# 14_-_BOT_BOARD_HEADER.net
KiCad netlist of a schematic drawn in Altium Designer
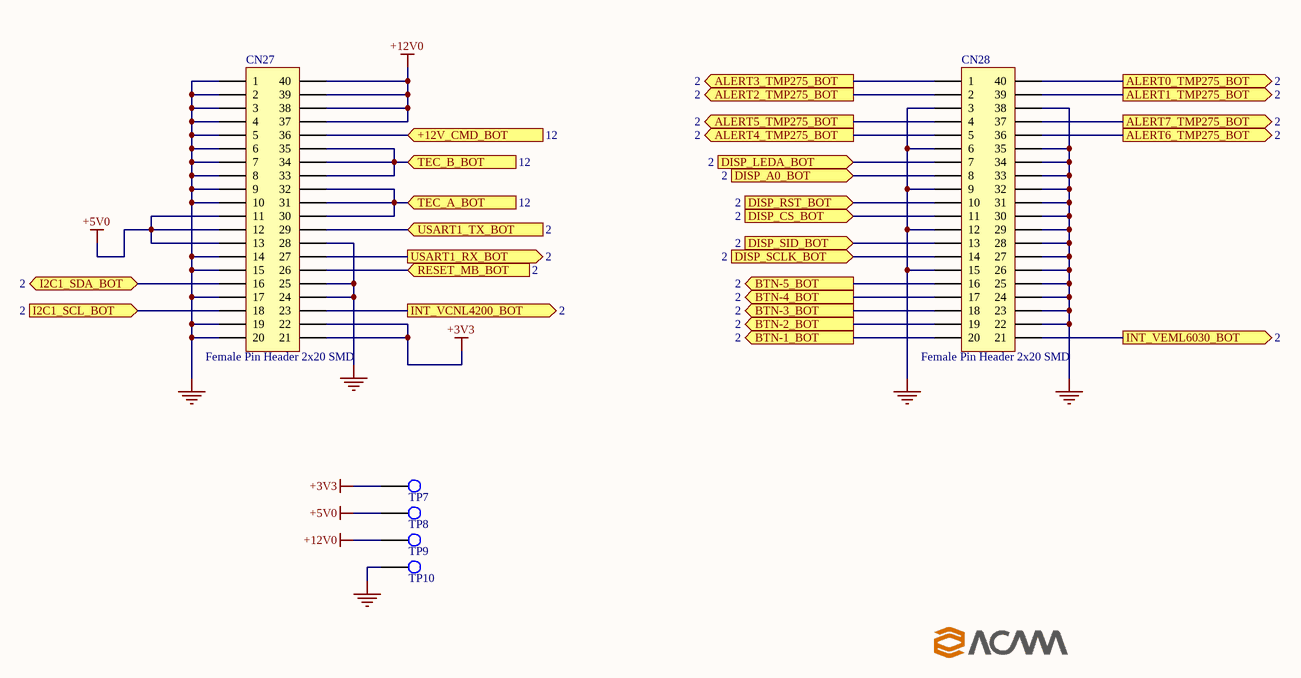
[diagram p0: [14] - BOT BOARD HEADER.SchDoc]

(export (version "E")
  (design (tool "Eeschema 10.0.6"))
  (components
    (comp (ref "CN27")
      (value "Female Pin Header 2x20 SMD")
      (footprint "HEADER_FEMALE_SMD_2x20")
      (description "SMD Female Pin Header 2.54mm Pitch, 2x20")
      (libsource (lib "Farzan Custom Library") (part "Pin header Female 2x20 smd"))
    )
    (comp (ref "CN28")
      (value "Female Pin Header 2x20 SMD")
      (footprint "HEADER_FEMALE_SMD_2x20")
      (description "SMD Female Pin Header 2.54mm Pitch, 2x20")
      (libsource (lib "Farzan Custom Library") (part "Pin header Female 2x20 smd"))
    )
    (comp (ref "TP7")
      (value "Test Point")
      (footprint "PIN_2mm")
      (description "Test Point Footprint")
      (libsource (lib "Farzan Custom Library") (part "Test Point"))
    )
    (comp (ref "TP8")
      (value "Test Point")
      (footprint "PIN_2mm")
      (description "Test Point Footprint")
      (libsource (lib "Farzan Custom Library") (part "Test Point"))
    )
    (comp (ref "TP9")
      (value "Test Point")
      (footprint "PIN_2mm")
      (description "Test Point Footprint")
      (libsource (lib "Farzan Custom Library") (part "Test Point"))
    )
    (comp (ref "TP10")
      (value "Test Point")
      (footprint "PIN_2mm")
      (description "Test Point Footprint")
      (libsource (lib "Farzan Custom Library") (part "Test Point"))
    )
  )
  (nets
    (net (code "1") (name "+3V3") (class "Default")
      (node (ref "CN27") (pin "21") (pinfunction "21_21") (pintype "passive"))
      (node (ref "CN27") (pin "22") (pinfunction "22_22") (pintype "passive"))
      (node (ref "TP7") (pin "1") (pinfunction "1_1") (pintype "power_in"))
    )
    (net (code "2") (name "+5V0") (class "Default")
      (node (ref "CN27") (pin "11") (pinfunction "11_11") (pintype "passive"))
      (node (ref "CN27") (pin "12") (pinfunction "12_12") (pintype "passive"))
      (node (ref "CN27") (pin "13") (pinfunction "13_13") (pintype "passive"))
      (node (ref "TP8") (pin "1") (pinfunction "1_1") (pintype "power_in"))
    )
    (net (code "3") (name "+12V0") (class "Default")
      (node (ref "CN27") (pin "37") (pinfunction "37_37") (pintype "passive"))
      (node (ref "CN27") (pin "38") (pinfunction "38_38") (pintype "passive"))
      (node (ref "CN27") (pin "39") (pinfunction "39_39") (pintype "passive"))
      (node (ref "CN27") (pin "40") (pinfunction "40_40") (pintype "passive"))
      (node (ref "TP9") (pin "1") (pinfunction "1_1") (pintype "power_in"))
    )
    (net (code "4") (name "/+12V_CMD_BOT") (class "Default")
      (node (ref "CN27") (pin "36") (pinfunction "36_36") (pintype "passive"))
    )
    (net (code "5") (name "/ALERT0_TMP275_BOT") (class "Default")
      (node (ref "CN28") (pin "40") (pinfunction "40_40") (pintype "passive"))
    )
    (net (code "6") (name "/ALERT1_TMP275_BOT") (class "Default")
      (node (ref "CN28") (pin "39") (pinfunction "39_39") (pintype "passive"))
    )
    (net (code "7") (name "/ALERT2_TMP275_BOT") (class "Default")
      (node (ref "CN28") (pin "2") (pinfunction "2_2") (pintype "passive"))
    )
    (net (code "8") (name "/ALERT3_TMP275_BOT") (class "Default")
      (node (ref "CN28") (pin "1") (pinfunction "1_1") (pintype "passive"))
    )
    (net (code "9") (name "/ALERT4_TMP275_BOT") (class "Default")
      (node (ref "CN28") (pin "5") (pinfunction "5_5") (pintype "passive"))
    )
    (net (code "10") (name "/ALERT5_TMP275_BOT") (class "Default")
      (node (ref "CN28") (pin "4") (pinfunction "4_4") (pintype "passive"))
    )
    (net (code "11") (name "/ALERT6_TMP275_BOT") (class "Default")
      (node (ref "CN28") (pin "36") (pinfunction "36_36") (pintype "passive"))
    )
    (net (code "12") (name "/ALERT7_TMP275_BOT") (class "Default")
      (node (ref "CN28") (pin "37") (pinfunction "37_37") (pintype "passive"))
    )
    (net (code "13") (name "/BTN-1_BOT") (class "Default")
      (node (ref "CN28") (pin "20") (pinfunction "20_20") (pintype "passive"))
    )
    (net (code "14") (name "/BTN-2_BOT") (class "Default")
      (node (ref "CN28") (pin "19") (pinfunction "19_19") (pintype "passive"))
    )
    (net (code "15") (name "/BTN-3_BOT") (class "Default")
      (node (ref "CN28") (pin "18") (pinfunction "18_18") (pintype "passive"))
    )
    (net (code "16") (name "/BTN-4_BOT") (class "Default")
      (node (ref "CN28") (pin "17") (pinfunction "17_17") (pintype "passive"))
    )
    (net (code "17") (name "/BTN-5_BOT") (class "Default")
      (node (ref "CN28") (pin "16") (pinfunction "16_16") (pintype "passive"))
    )
    (net (code "18") (name "/DISP_A0_BOT") (class "Default")
      (node (ref "CN28") (pin "8") (pinfunction "8_8") (pintype "passive"))
    )
    (net (code "19") (name "/DISP_CS_BOT") (class "Default")
      (node (ref "CN28") (pin "11") (pinfunction "11_11") (pintype "passive"))
    )
    (net (code "20") (name "/DISP_LEDA_BOT") (class "Default")
      (node (ref "CN28") (pin "7") (pinfunction "7_7") (pintype "passive"))
    )
    (net (code "21") (name "/DISP_RST_BOT") (class "Default")
      (node (ref "CN28") (pin "10") (pinfunction "10_10") (pintype "passive"))
    )
    (net (code "22") (name "/DISP_SCLK_BOT") (class "Default")
      (node (ref "CN28") (pin "14") (pinfunction "14_14") (pintype "passive"))
    )
    (net (code "23") (name "/DISP_SID_BOT") (class "Default")
      (node (ref "CN28") (pin "13") (pinfunction "13_13") (pintype "passive"))
    )
    (net (code "24") (name "/I2C1_SCL_BOT") (class "Default")
      (node (ref "CN27") (pin "18") (pinfunction "18_18") (pintype "passive"))
    )
    (net (code "25") (name "/I2C1_SDA_BOT") (class "Default")
      (node (ref "CN27") (pin "16") (pinfunction "16_16") (pintype "passive"))
    )
    (net (code "26") (name "/INT_VCNL4200_BOT") (class "Default")
      (node (ref "CN27") (pin "23") (pinfunction "23_23") (pintype "passive"))
    )
    (net (code "27") (name "/INT_VEML6030_BOT") (class "Default")
      (node (ref "CN28") (pin "21") (pinfunction "21_21") (pintype "passive"))
    )
    (net (code "28") (name "/RESET_MB_BOT") (class "Default")
      (node (ref "CN27") (pin "26") (pinfunction "26_26") (pintype "passive"))
    )
    (net (code "29") (name "/TEC_A_BOT") (class "Default")
      (node (ref "CN27") (pin "30") (pinfunction "30_30") (pintype "passive"))
      (node (ref "CN27") (pin "31") (pinfunction "31_31") (pintype "passive"))
      (node (ref "CN27") (pin "32") (pinfunction "32_32") (pintype "passive"))
    )
    (net (code "30") (name "/TEC_B_BOT") (class "Default")
      (node (ref "CN27") (pin "33") (pinfunction "33_33") (pintype "passive"))
      (node (ref "CN27") (pin "34") (pinfunction "34_34") (pintype "passive"))
      (node (ref "CN27") (pin "35") (pinfunction "35_35") (pintype "passive"))
    )
    (net (code "31") (name "/USART1_RX_BOT") (class "Default")
      (node (ref "CN27") (pin "27") (pinfunction "27_27") (pintype "passive"))
    )
    (net (code "32") (name "/USART1_TX_BOT") (class "Default")
      (node (ref "CN27") (pin "29") (pinfunction "29_29") (pintype "passive"))
    )
    (net (code "33") (name "GND") (class "Default")
      (node (ref "CN27") (pin "1") (pinfunction "1_1") (pintype "passive"))
      (node (ref "CN27") (pin "10") (pinfunction "10_10") (pintype "passive"))
      (node (ref "CN27") (pin "14") (pinfunction "14_14") (pintype "passive"))
      (node (ref "CN27") (pin "15") (pinfunction "15_15") (pintype "passive"))
      (node (ref "CN27") (pin "17") (pinfunction "17_17") (pintype "passive"))
      (node (ref "CN27") (pin "19") (pinfunction "19_19") (pintype "passive"))
      (node (ref "CN27") (pin "2") (pinfunction "2_2") (pintype "passive"))
      (node (ref "CN27") (pin "20") (pinfunction "20_20") (pintype "passive"))
      (node (ref "CN27") (pin "24") (pinfunction "24_24") (pintype "passive"))
      (node (ref "CN27") (pin "25") (pinfunction "25_25") (pintype "passive"))
      (node (ref "CN27") (pin "28") (pinfunction "28_28") (pintype "passive"))
      (node (ref "CN27") (pin "3") (pinfunction "3_3") (pintype "passive"))
      (node (ref "CN27") (pin "4") (pinfunction "4_4") (pintype "passive"))
      (node (ref "CN27") (pin "5") (pinfunction "5_5") (pintype "passive"))
      (node (ref "CN27") (pin "6") (pinfunction "6_6") (pintype "passive"))
      (node (ref "CN27") (pin "7") (pinfunction "7_7") (pintype "passive"))
      (node (ref "CN27") (pin "8") (pinfunction "8_8") (pintype "passive"))
      (node (ref "CN27") (pin "9") (pinfunction "9_9") (pintype "passive"))
      (node (ref "CN28") (pin "12") (pinfunction "12_12") (pintype "passive"))
      (node (ref "CN28") (pin "15") (pinfunction "15_15") (pintype "passive"))
      (node (ref "CN28") (pin "22") (pinfunction "22_22") (pintype "passive"))
      (node (ref "CN28") (pin "23") (pinfunction "23_23") (pintype "passive"))
      (node (ref "CN28") (pin "24") (pinfunction "24_24") (pintype "passive"))
      (node (ref "CN28") (pin "25") (pinfunction "25_25") (pintype "passive"))
      (node (ref "CN28") (pin "26") (pinfunction "26_26") (pintype "passive"))
      (node (ref "CN28") (pin "27") (pinfunction "27_27") (pintype "passive"))
      (node (ref "CN28") (pin "28") (pinfunction "28_28") (pintype "passive"))
      (node (ref "CN28") (pin "29") (pinfunction "29_29") (pintype "passive"))
      (node (ref "CN28") (pin "3") (pinfunction "3_3") (pintype "passive"))
      (node (ref "CN28") (pin "30") (pinfunction "30_30") (pintype "passive"))
      (node (ref "CN28") (pin "31") (pinfunction "31_31") (pintype "passive"))
      (node (ref "CN28") (pin "32") (pinfunction "32_32") (pintype "passive"))
      (node (ref "CN28") (pin "33") (pinfunction "33_33") (pintype "passive"))
      (node (ref "CN28") (pin "34") (pinfunction "34_34") (pintype "passive"))
      (node (ref "CN28") (pin "35") (pinfunction "35_35") (pintype "passive"))
      (node (ref "CN28") (pin "38") (pinfunction "38_38") (pintype "passive"))
      (node (ref "CN28") (pin "6") (pinfunction "6_6") (pintype "passive"))
      (node (ref "CN28") (pin "9") (pinfunction "9_9") (pintype "passive"))
      (node (ref "TP10") (pin "1") (pinfunction "1_1") (pintype "power_in"))
    )
  )
)
